# child.net
KiCad netlist of a schematic drawn in Altium Designer
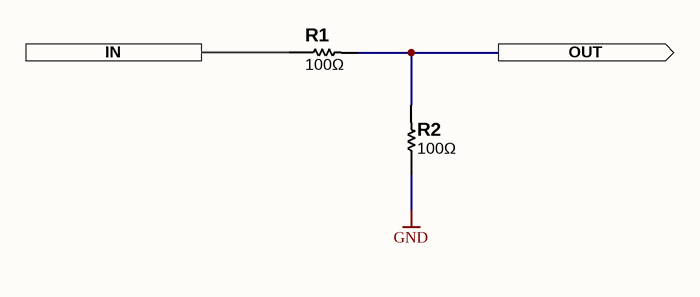
[diagram p0: child.SchDoc]

(export (version "E")
  (design (tool "Eeschema 10.0.6"))
  (components
    (comp (ref "R1")
      (value "100Ω")
      (footprint "R0603_0.55MM_HD")
      (description "RES 100 OHM 1/10W 1% 0603 SMD")
      (fields
        (field (name "TOLERANCE") "±1%")
        (field (name "MANUFACTURER") "Panasonic Electronic Components")
      )
      (libsource (lib "wavenumber") (part "R_2P"))
    )
    (comp (ref "R2")
      (value "100Ω")
      (footprint "R0603_0.55MM_HD")
      (description "RES 100 OHM 1/10W 1% 0603 SMD")
      (fields
        (field (name "TOLERANCE") "±1%")
        (field (name "MANUFACTURER") "Panasonic Electronic Components")
      )
      (libsource (lib "wavenumber") (part "R_2P"))
    )
  )
  (nets
    (net (code "1") (name "/IN") (class "Default")
      (node (ref "R1") (pin "1") (pinfunction "1_1") (pintype "passive"))
    )
    (net (code "2") (name "/OUT") (class "Default")
      (node (ref "R1") (pin "2") (pinfunction "2_2") (pintype "passive"))
      (node (ref "R2") (pin "2") (pinfunction "2_2") (pintype "passive"))
    )
    (net (code "3") (name "GND") (class "Default")
      (node (ref "R2") (pin "1") (pinfunction "1_1") (pintype "passive"))
    )
  )
)
